# Addon-mapleCUx_HM-RFM69-RFM95-V15-001-TX.net
KiCad netlist of a schematic drawn in EAGLE
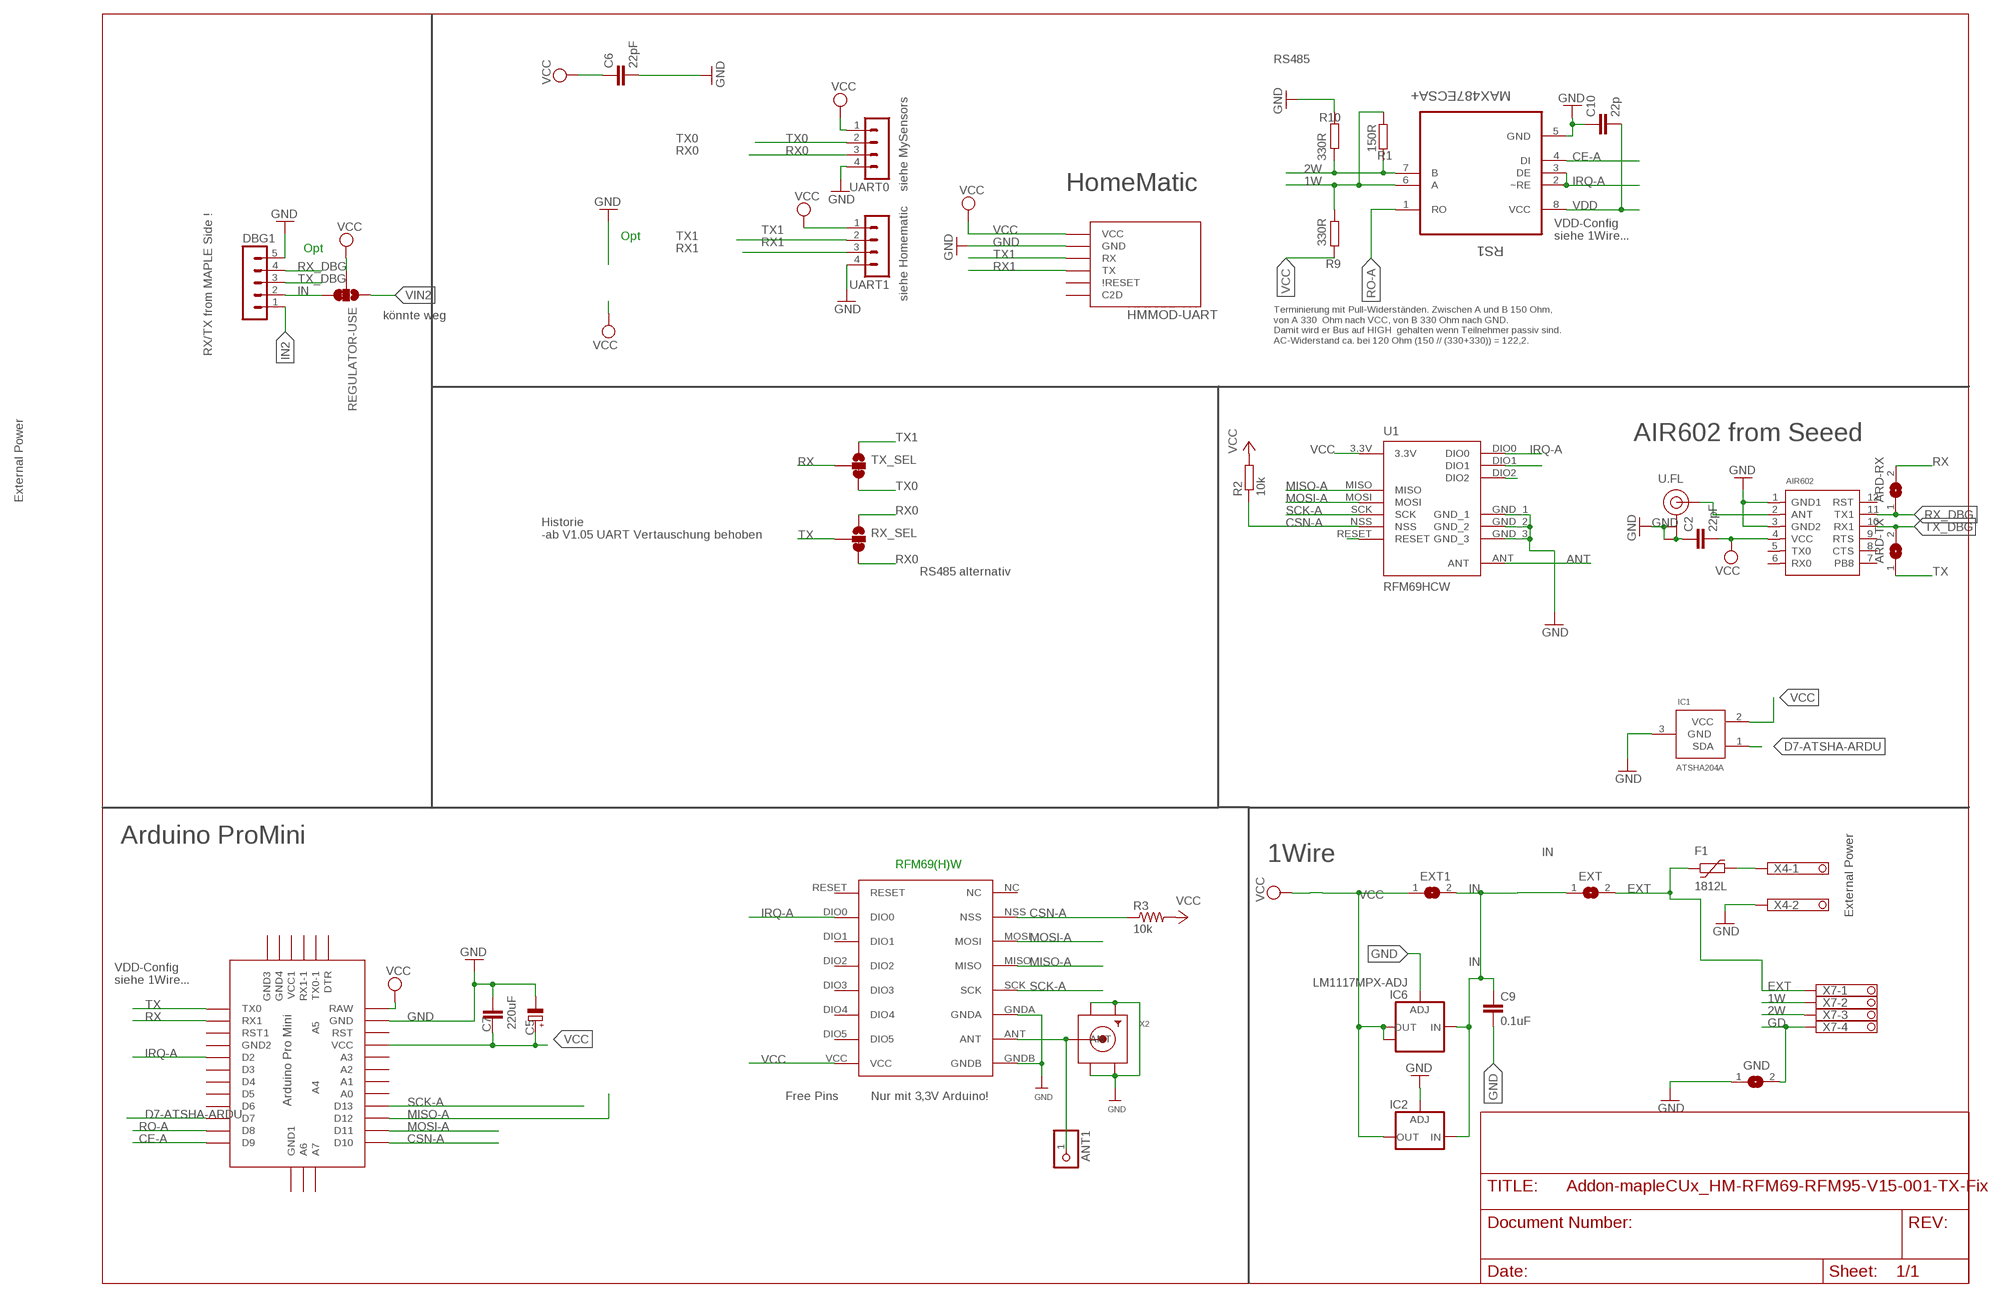
[diagram p0: schematic, sheet 1]

(export (version "E")
  (design (tool "Eeschema 10.0.6"))
  (components
    (comp (ref "AIR602")
      (value "AIR602")
      (footprint "eagle-import:MODULE12P-2.0-10X12MM")
      (libsource (lib "eagle-import") (part "AIR602"))
    )
    (comp (ref "ANT1")
      (value "PINHD-1X1")
      (footprint "eagle-import:1X01")
      (libsource (lib "eagle-import") (part "PINHD-1X1"))
    )
    (comp (ref "ARD-RX")
      (value "SJ")
      (footprint "eagle-import:SJ")
      (libsource (lib "eagle-import") (part "SJ"))
    )
    (comp (ref "ARD-TX")
      (value "SJ")
      (footprint "eagle-import:SJ")
      (libsource (lib "eagle-import") (part "SJ"))
    )
    (comp (ref "C2")
      (value "22pF")
      (footprint "eagle-import:C0805")
      (libsource (lib "eagle-import") (part "C-EUC0805"))
    )
    (comp (ref "C5")
      (value "220uF")
      (footprint "eagle-import:E5-8,5")
      (libsource (lib "eagle-import") (part "CPOL-EUE5-8.5"))
    )
    (comp (ref "C6")
      (value "22pF")
      (footprint "eagle-import:C0805")
      (libsource (lib "eagle-import") (part "C-EUC0805"))
    )
    (comp (ref "C7")
      (value "C-EUC1812")
      (footprint "eagle-import:C1812")
      (libsource (lib "eagle-import") (part "C-EUC1812"))
    )
    (comp (ref "C9")
      (value "0.1uF")
      (footprint "eagle-import:C1206")
      (libsource (lib "eagle-import") (part "C-EUC1206"))
    )
    (comp (ref "C10")
      (value "22p")
      (footprint "eagle-import:C0805")
      (libsource (lib "eagle-import") (part "C-EUC0805"))
    )
    (comp (ref "DBG1")
      (value "MA05-1")
      (footprint "eagle-import:MA05-1")
      (libsource (lib "eagle-import") (part "MA05-1"))
    )
    (comp (ref "EXT") (value "SJ") (footprint "eagle-import:SJ") (libsource (lib "eagle-import") (part "SJ")))
    (comp (ref "EXT1")
      (value "SJ")
      (footprint "eagle-import:SJ")
      (libsource (lib "eagle-import") (part "SJ"))
    )
    (comp (ref "F1")
      (value "1812L")
      (footprint "eagle-import:1812L")
      (libsource (lib "eagle-import") (part "1812L"))
    )
    (comp (ref "GND") (value "SJ") (footprint "eagle-import:SJ") (libsource (lib "eagle-import") (part "SJ")))
    (comp (ref "HMMOD-UART")
      (value "HM-MOD-UARTDIL")
      (footprint "eagle-import:HM-MOD-UART-DIL")
      (libsource (lib "eagle-import") (part "HM-MOD-UARTDIL"))
    )
    (comp (ref "IC1")
      (value "ATSHA204A")
      (footprint "eagle-import:SOT23")
      (libsource (lib "eagle-import") (part "ATSHA204A"))
    )
    (comp (ref "IC2")
      (value "LD117ADT50TR")
      (footprint "eagle-import:DPACK")
      (libsource (lib "eagle-import") (part "LD117A?DT50TR"))
    )
    (comp (ref "IC6")
      (value "LM1117MPX-ADJ")
      (footprint "eagle-import:SOT223")
      (libsource (lib "eagle-import") (part "LM1117MPX-ADJ"))
    )
    (comp (ref "R1")
      (value "150R")
      (footprint "eagle-import:R0805")
      (libsource (lib "eagle-import") (part "R-EU_R0805"))
    )
    (comp (ref "R2")
      (value "10k")
      (footprint "eagle-import:M0805")
      (libsource (lib "eagle-import") (part "R-EU_M0805"))
    )
    (comp (ref "R3")
      (value "10k")
      (footprint "eagle-import:0805")
      (libsource (lib "eagle-import") (part "RESISTOR0805-RES"))
    )
    (comp (ref "R9")
      (value "330R")
      (footprint "eagle-import:R0805")
      (libsource (lib "eagle-import") (part "R-EU_R0805"))
    )
    (comp (ref "R10")
      (value "330R")
      (footprint "eagle-import:R0805")
      (libsource (lib "eagle-import") (part "R-EU_R0805"))
    )
    (comp (ref "REGULATOR-USE")
      (value "JUMPER-SMT_3_1-NC_TRACE_SILK")
      (footprint "eagle-import:SMT-JUMPER_3_1-NC_TRACE_SILK")
      (libsource (lib "eagle-import") (part "JUMPER-SMT_3_1-NC_TRACE_SILK"))
    )
    (comp (ref "RFM69W")
      (value "RFM69HW")
      (footprint "eagle-import:RFM")
      (libsource (lib "eagle-import") (part "RFM69HW"))
    )
    (comp (ref "RS1")
      (value "MAX487ECSA+")
      (footprint "eagle-import:SOIC127P600X175-8N")
      (libsource (lib "eagle-import") (part "MAX487ECSA+"))
    )
    (comp (ref "RX_SEL")
      (value "JUMPER-SMT_3_1-NC_TRACE_SILK")
      (footprint "eagle-import:SMT-JUMPER_3_1-NC_TRACE_SILK")
      (libsource (lib "eagle-import") (part "JUMPER-SMT_3_1-NC_TRACE_SILK"))
    )
    (comp (ref "TX_SEL")
      (value "JUMPER-SMT_3_1-NC_TRACE_SILK")
      (footprint "eagle-import:SMT-JUMPER_3_1-NC_TRACE_SILK")
      (libsource (lib "eagle-import") (part "JUMPER-SMT_3_1-NC_TRACE_SILK"))
    )
    (comp (ref "U$2")
      (value "ABK-PRO-MINI")
      (footprint "eagle-import:ABK-PRO-MINI")
      (libsource (lib "eagle-import") (part "ABK-PRO-MINI"))
    )
    (comp (ref "U.FL")
      (value "U.FL")
      (footprint "eagle-import:U.FL")
      (libsource (lib "eagle-import") (part "U.FL"))
    )
    (comp (ref "U1")
      (value "RFM69HCW")
      (footprint "eagle-import:RFM69HCW-XXXS2")
      (libsource (lib "eagle-import") (part "RFM69HCW"))
    )
    (comp (ref "UART0")
      (value "MA04-1")
      (footprint "eagle-import:MA04-1")
      (libsource (lib "eagle-import") (part "MA04-1"))
    )
    (comp (ref "UART1")
      (value "MA04-1")
      (footprint "eagle-import:MA04-1")
      (libsource (lib "eagle-import") (part "MA04-1"))
    )
    (comp (ref "X2")
      (value "SMACONNECTOR_EDGE")
      (footprint "eagle-import:SMA_EDGELAUNCH")
      (libsource (lib "eagle-import") (part "SMACONNECTOR_EDGE"))
    )
    (comp (ref "X4")
      (value "1751248")
      (footprint "eagle-import:1751248")
      (libsource (lib "eagle-import") (part "1751248"))
    )
    (comp (ref "X7")
      (value "1751264")
      (footprint "eagle-import:1751264")
      (libsource (lib "eagle-import") (part "1751264"))
    )
  )
  (nets
    (net (code "1") (name "/1W") (class "Default")
      (node (ref "R1") (pin "1") (pinfunction "1_1") (pintype "passive"))
      (node (ref "R9") (pin "2") (pinfunction "2_2") (pintype "passive"))
      (node (ref "RS1") (pin "6") (pinfunction "A_6") (pintype "bidirectional"))
      (node (ref "X7") (pin "2") (pinfunction "K_2") (pintype "passive"))
    )
    (net (code "2") (name "/2W") (class "Default")
      (node (ref "R1") (pin "2") (pinfunction "2_2") (pintype "passive"))
      (node (ref "R10") (pin "1") (pinfunction "1_1") (pintype "passive"))
      (node (ref "RS1") (pin "7") (pinfunction "B_7") (pintype "bidirectional"))
      (node (ref "X7") (pin "3") (pinfunction "K_3") (pintype "passive"))
    )
    (net (code "3") (name "/ANT") (class "Default")
      (node (ref "ANT1") (pin "1") (pinfunction "1_1") (pintype "passive"))
      (node (ref "RFM69W") (pin "ANT") (pinfunction "ANT_ANT") (pintype "bidirectional"))
      (node (ref "U1") (pin "ANT") (pinfunction "ANT_ANT") (pintype "passive"))
      (node (ref "X2") (pin "P") (pinfunction "ANT_P") (pintype "bidirectional"))
    )
    (net (code "4") (name "/CE-A") (class "Default")
      (node (ref "RS1") (pin "4") (pinfunction "DI_4") (pintype "input"))
      (node (ref "U$2") (pin "D9") (pinfunction "D9_D9") (pintype "bidirectional"))
    )
    (net (code "5") (name "/CSN-A") (class "Default")
      (node (ref "R2") (pin "1") (pinfunction "1_1") (pintype "passive"))
      (node (ref "R3") (pin "1") (pinfunction "1_1") (pintype "passive"))
      (node (ref "RFM69W") (pin "NSS") (pinfunction "NSS_NSS") (pintype "bidirectional"))
      (node (ref "U$2") (pin "D10") (pinfunction "D10_D10") (pintype "bidirectional"))
      (node (ref "U1") (pin "NSS") (pinfunction "NSS_NSS") (pintype "input"))
    )
    (net (code "6") (name "/EXT") (class "Default")
      (node (ref "EXT") (pin "2") (pinfunction "2_2") (pintype "passive"))
      (node (ref "F1") (pin "P$1") (pinfunction "1_P$1") (pintype "passive"))
      (node (ref "X7") (pin "1") (pinfunction "K_1") (pintype "passive"))
    )
    (net (code "7") (name "/GD") (class "Default")
      (node (ref "GND") (pin "2") (pinfunction "2_2") (pintype "passive"))
      (node (ref "X7") (pin "4") (pinfunction "K_4") (pintype "passive"))
    )
    (net (code "8") (name "/IN") (class "Default")
      (node (ref "C9") (pin "1") (pinfunction "1_1") (pintype "passive"))
      (node (ref "DBG1") (pin "2") (pinfunction "2_2") (pintype "passive"))
      (node (ref "EXT") (pin "1") (pinfunction "1_1") (pintype "passive"))
      (node (ref "EXT1") (pin "2") (pinfunction "2_2") (pintype "passive"))
      (node (ref "IC2") (pin "3") (pinfunction "IN_3") (pintype "input"))
      (node (ref "IC6") (pin "3") (pinfunction "IN_3") (pintype "input"))
      (node (ref "REGULATOR-USE") (pin "3") (pinfunction "3_3") (pintype "passive"))
    )
    (net (code "9") (name "/IRQ-A") (class "Default")
      (node (ref "RFM69W") (pin "DIO0") (pinfunction "DIO0_DIO0") (pintype "bidirectional"))
      (node (ref "RS1") (pin "2") (pinfunction "~{RE}_2") (pintype "input"))
      (node (ref "RS1") (pin "3") (pinfunction "DE_3") (pintype "input"))
      (node (ref "U$2") (pin "D2") (pinfunction "D2_D2") (pintype "bidirectional"))
      (node (ref "U1") (pin "DIO0") (pinfunction "DIO0_DIO0") (pintype "bidirectional"))
    )
    (net (code "10") (name "/MISO-A") (class "Default")
      (node (ref "RFM69W") (pin "MISO") (pinfunction "MISO_MISO") (pintype "bidirectional"))
      (node (ref "U$2") (pin "D12") (pinfunction "D12_D12") (pintype "bidirectional"))
      (node (ref "U1") (pin "MISO") (pinfunction "MISO_MISO") (pintype "bidirectional"))
    )
    (net (code "11") (name "/MOSI-A") (class "Default")
      (node (ref "RFM69W") (pin "MOSI") (pinfunction "MOSI_MOSI") (pintype "bidirectional"))
      (node (ref "U$2") (pin "D11") (pinfunction "D11_D11") (pintype "bidirectional"))
      (node (ref "U1") (pin "MOSI") (pinfunction "MOSI_MOSI") (pintype "input"))
    )
    (net (code "12") (name "/RX") (class "Default")
      (node (ref "ARD-RX") (pin "2") (pinfunction "2_2") (pintype "passive"))
      (node (ref "TX_SEL") (pin "2") (pinfunction "2_2") (pintype "passive"))
      (node (ref "U$2") (pin "RX1") (pinfunction "RX1_RX1") (pintype "bidirectional"))
    )
    (net (code "13") (name "/RX0") (class "Default")
      (node (ref "RX_SEL") (pin "1") (pinfunction "1_1") (pintype "passive"))
      (node (ref "RX_SEL") (pin "3") (pinfunction "3_3") (pintype "passive"))
      (node (ref "UART0") (pin "3") (pinfunction "3_3") (pintype "passive"))
    )
    (net (code "14") (name "/RX1") (class "Default")
      (node (ref "HMMOD-UART") (pin "5") (pinfunction "TX_5") (pintype "bidirectional"))
      (node (ref "UART1") (pin "3") (pinfunction "3_3") (pintype "passive"))
    )
    (net (code "15") (name "/SCK-A") (class "Default")
      (node (ref "RFM69W") (pin "SCK") (pinfunction "SCK_SCK") (pintype "bidirectional"))
      (node (ref "U$2") (pin "D13") (pinfunction "D13_D13") (pintype "bidirectional"))
      (node (ref "U1") (pin "SCK") (pinfunction "SCK_SCK") (pintype "input"))
    )
    (net (code "16") (name "/TX") (class "Default")
      (node (ref "ARD-TX") (pin "1") (pinfunction "1_1") (pintype "passive"))
      (node (ref "RX_SEL") (pin "2") (pinfunction "2_2") (pintype "passive"))
      (node (ref "U$2") (pin "TX0") (pinfunction "TX0_TX0") (pintype "bidirectional"))
    )
    (net (code "17") (name "/TX0") (class "Default")
      (node (ref "TX_SEL") (pin "3") (pinfunction "3_3") (pintype "passive"))
      (node (ref "UART0") (pin "2") (pinfunction "2_2") (pintype "passive"))
    )
    (net (code "18") (name "/TX1") (class "Default")
      (node (ref "HMMOD-UART") (pin "6") (pinfunction "RX_6") (pintype "bidirectional"))
      (node (ref "TX_SEL") (pin "1") (pinfunction "1_1") (pintype "passive"))
      (node (ref "UART1") (pin "2") (pinfunction "2_2") (pintype "passive"))
    )
    (net (code "19") (name "/VDD") (class "Default")
      (node (ref "C10") (pin "2") (pinfunction "2_2") (pintype "passive"))
      (node (ref "RS1") (pin "8") (pinfunction "VCC_8") (pintype "power_in"))
    )
    (net (code "20") (name "D7-ATSHA-ARDU") (class "Default")
      (node (ref "IC1") (pin "1") (pinfunction "SDA_1") (pintype "bidirectional"))
      (node (ref "U$2") (pin "D7") (pinfunction "D7_D7") (pintype "bidirectional"))
    )
    (net (code "21") (name "GND") (class "Default")
      (node (ref "AIR602") (pin "1") (pinfunction "GND1_1") (pintype "bidirectional"))
      (node (ref "AIR602") (pin "3") (pinfunction "GND2_3") (pintype "bidirectional"))
      (node (ref "C10") (pin "1") (pinfunction "1_1") (pintype "passive"))
      (node (ref "C2") (pin "1") (pinfunction "1_1") (pintype "passive"))
      (node (ref "C5") (pin "-") (pinfunction "-_-") (pintype "passive"))
      (node (ref "C6") (pin "2") (pinfunction "2_2") (pintype "passive"))
      (node (ref "C7") (pin "1") (pinfunction "1_1") (pintype "passive"))
      (node (ref "C9") (pin "2") (pinfunction "2_2") (pintype "passive"))
      (node (ref "DBG1") (pin "5") (pinfunction "5_5") (pintype "passive"))
      (node (ref "GND") (pin "1") (pinfunction "1_1") (pintype "passive"))
      (node (ref "HMMOD-UART") (pin "2") (pinfunction "GND_2") (pintype "power_in"))
      (node (ref "IC1") (pin "3") (pinfunction "GND_3") (pintype "bidirectional"))
      (node (ref "IC2") (pin "1") (pinfunction "ADJ_1") (pintype "input"))
      (node (ref "IC6") (pin "1") (pinfunction "ADJ_1") (pintype "input"))
      (node (ref "R10") (pin "2") (pinfunction "2_2") (pintype "passive"))
      (node (ref "RFM69W") (pin "GNDA") (pinfunction "GNDA_GNDA") (pintype "bidirectional"))
      (node (ref "RFM69W") (pin "GNDB") (pinfunction "GNDB_GNDB") (pintype "bidirectional"))
      (node (ref "RS1") (pin "5") (pinfunction "GND_5") (pintype "passive"))
      (node (ref "U$2") (pin "GND") (pinfunction "GND_GND") (pintype "bidirectional"))
      (node (ref "U.FL") (pin "1") (pinfunction "GND_1") (pintype "bidirectional"))
      (node (ref "U.FL") (pin "2") (pinfunction "GND_2") (pintype "bidirectional"))
      (node (ref "U1") (pin "GND_1") (pinfunction "GND_1_GND_1") (pintype "power_in"))
      (node (ref "U1") (pin "GND_2") (pinfunction "GND_2_GND_2") (pintype "power_in"))
      (node (ref "U1") (pin "GND_3") (pinfunction "GND_3_GND_3") (pintype "power_in"))
      (node (ref "UART0") (pin "4") (pinfunction "4_4") (pintype "passive"))
      (node (ref "UART1") (pin "4") (pinfunction "4_4") (pintype "passive"))
      (node (ref "X2") (pin "GND@1") (pinfunction "GND4_GND@1") (pintype "power_in"))
      (node (ref "X2") (pin "GND@2") (pinfunction "GND3_GND@2") (pintype "power_in"))
      (node (ref "X2") (pin "GND@3") (pinfunction "GND2_GND@3") (pintype "power_in"))
      (node (ref "X2") (pin "GND@4") (pinfunction "GND1_GND@4") (pintype "power_in"))
      (node (ref "X4") (pin "2") (pinfunction "K_2") (pintype "passive"))
    )
    (net (code "22") (name "IN2") (class "Default")
      (node (ref "DBG1") (pin "1") (pinfunction "1_1") (pintype "passive"))
    )
    (net (code "23") (name "Net-(AIR602-ANT)") (class "Default")
      (node (ref "AIR602") (pin "2") (pinfunction "ANT_2") (pintype "bidirectional"))
      (node (ref "U.FL") (pin "FEED") (pinfunction "SIGNAL_FEED") (pintype "bidirectional"))
    )
    (net (code "24") (name "Net-(F1-2)") (class "Default")
      (node (ref "F1") (pin "P$2") (pinfunction "2_P$2") (pintype "passive"))
      (node (ref "X4") (pin "1") (pinfunction "K_1") (pintype "passive"))
    )
    (net (code "25") (name "RO-A") (class "Default")
      (node (ref "RS1") (pin "1") (pinfunction "RO_1") (pintype "output"))
      (node (ref "U$2") (pin "D8") (pinfunction "D8_D8") (pintype "bidirectional"))
    )
    (net (code "26") (name "RX_DBG") (class "Default")
      (node (ref "AIR602") (pin "11") (pinfunction "TX1_11") (pintype "bidirectional"))
      (node (ref "ARD-RX") (pin "1") (pinfunction "1_1") (pintype "passive"))
      (node (ref "DBG1") (pin "4") (pinfunction "4_4") (pintype "passive"))
    )
    (net (code "27") (name "TX_DBG") (class "Default")
      (node (ref "AIR602") (pin "10") (pinfunction "RX1_10") (pintype "bidirectional"))
      (node (ref "ARD-TX") (pin "2") (pinfunction "2_2") (pintype "passive"))
      (node (ref "DBG1") (pin "3") (pinfunction "3_3") (pintype "passive"))
    )
    (net (code "28") (name "VCC") (class "Default")
      (node (ref "AIR602") (pin "4") (pinfunction "VCC_4") (pintype "bidirectional"))
      (node (ref "C2") (pin "2") (pinfunction "2_2") (pintype "passive"))
      (node (ref "C5") (pin "+") (pinfunction "+_+") (pintype "passive"))
      (node (ref "C6") (pin "1") (pinfunction "1_1") (pintype "passive"))
      (node (ref "C7") (pin "2") (pinfunction "2_2") (pintype "passive"))
      (node (ref "EXT1") (pin "1") (pinfunction "1_1") (pintype "passive"))
      (node (ref "HMMOD-UART") (pin "1") (pinfunction "VCC_1") (pintype "power_in"))
      (node (ref "IC1") (pin "2") (pinfunction "VCC_2") (pintype "bidirectional"))
      (node (ref "IC2") (pin "4") (pinfunction "OUT_4") (pintype "passive"))
      (node (ref "IC6") (pin "2") (pinfunction "OUT_2") (pintype "passive"))
      (node (ref "IC6") (pin "TAB") (pinfunction "OUT1_TAB") (pintype "passive"))
      (node (ref "R2") (pin "2") (pinfunction "2_2") (pintype "passive"))
      (node (ref "R3") (pin "2") (pinfunction "2_2") (pintype "passive"))
      (node (ref "R9") (pin "1") (pinfunction "1_1") (pintype "passive"))
      (node (ref "REGULATOR-USE") (pin "2") (pinfunction "2_2") (pintype "passive"))
      (node (ref "RFM69W") (pin "VCC") (pinfunction "VCC_VCC") (pintype "bidirectional"))
      (node (ref "U$2") (pin "RAW") (pinfunction "RAW_RAW") (pintype "bidirectional"))
      (node (ref "U$2") (pin "VCC") (pinfunction "VCC_VCC") (pintype "bidirectional"))
      (node (ref "U1") (pin "3.3V") (pinfunction "3.3V_3.3V") (pintype "power_in"))
      (node (ref "UART0") (pin "1") (pinfunction "1_1") (pintype "passive"))
      (node (ref "UART1") (pin "1") (pinfunction "1_1") (pintype "passive"))
    )
    (net (code "29") (name "VIN2") (class "Default")
      (node (ref "REGULATOR-USE") (pin "1") (pinfunction "1_1") (pintype "passive"))
    )
    (net (code "30") (name "unconnected-(AIR602-CTS-Pad8)") (class "Default")
      (node (ref "AIR602") (pin "8") (pinfunction "CTS_8") (pintype "bidirectional"))
    )
    (net (code "31") (name "unconnected-(AIR602-PB8-Pad7)") (class "Default")
      (node (ref "AIR602") (pin "7") (pinfunction "PB8_7") (pintype "bidirectional"))
    )
    (net (code "32") (name "unconnected-(AIR602-RST-Pad12)") (class "Default")
      (node (ref "AIR602") (pin "12") (pinfunction "RST_12") (pintype "bidirectional"))
    )
    (net (code "33") (name "unconnected-(AIR602-RTS-Pad9)") (class "Default")
      (node (ref "AIR602") (pin "9") (pinfunction "RTS_9") (pintype "bidirectional"))
    )
    (net (code "34") (name "unconnected-(AIR602-RX0-Pad6)") (class "Default")
      (node (ref "AIR602") (pin "6") (pinfunction "RX0_6") (pintype "bidirectional"))
    )
    (net (code "35") (name "unconnected-(AIR602-TX0-Pad5)") (class "Default")
      (node (ref "AIR602") (pin "5") (pinfunction "TX0_5") (pintype "bidirectional"))
    )
    (net (code "36") (name "unconnected-(HMMOD-UART-C2D-Pad3)") (class "Default")
      (node (ref "HMMOD-UART") (pin "3") (pinfunction "C2D_3") (pintype "bidirectional"))
    )
    (net (code "37") (name "unconnected-(HMMOD-UART-\\~{RESET}-Pad4)") (class "Default")
      (node (ref "HMMOD-UART") (pin "4") (pinfunction "\\~{RESET}_4") (pintype "bidirectional"))
    )
    (net (code "38") (name "unconnected-(RFM69W-PadDIO1)") (class "Default")
      (node (ref "RFM69W") (pin "DIO1") (pinfunction "DIO1_DIO1") (pintype "bidirectional"))
    )
    (net (code "39") (name "unconnected-(RFM69W-PadDIO2)") (class "Default")
      (node (ref "RFM69W") (pin "DIO2") (pinfunction "DIO2_DIO2") (pintype "bidirectional"))
    )
    (net (code "40") (name "unconnected-(RFM69W-PadDIO3)") (class "Default")
      (node (ref "RFM69W") (pin "DIO3") (pinfunction "DIO3_DIO3") (pintype "bidirectional"))
    )
    (net (code "41") (name "unconnected-(RFM69W-PadDIO4)") (class "Default")
      (node (ref "RFM69W") (pin "DIO4") (pinfunction "DIO4_DIO4") (pintype "bidirectional"))
    )
    (net (code "42") (name "unconnected-(RFM69W-PadDIO5)") (class "Default")
      (node (ref "RFM69W") (pin "DIO5") (pinfunction "DIO5_DIO5") (pintype "bidirectional"))
    )
    (net (code "43") (name "unconnected-(RFM69W-PadNC)") (class "Default")
      (node (ref "RFM69W") (pin "NC") (pinfunction "NC_NC") (pintype "bidirectional"))
    )
    (net (code "44") (name "unconnected-(RFM69W-PadRESET)") (class "Default")
      (node (ref "RFM69W") (pin "RESET") (pinfunction "RESET_RESET") (pintype "bidirectional"))
    )
    (net (code "45") (name "unconnected-(U$2-GND1-PadGND4)") (class "Default")
      (node (ref "U$2") (pin "GND4") (pinfunction "GND1_GND4") (pintype "bidirectional"))
    )
    (net (code "46") (name "unconnected-(U$2-GND2-PadGND1)") (class "Default")
      (node (ref "U$2") (pin "GND1") (pinfunction "GND2_GND1") (pintype "bidirectional"))
    )
    (net (code "47") (name "unconnected-(U$2-GND3-PadGND2)") (class "Default")
      (node (ref "U$2") (pin "GND2") (pinfunction "GND3_GND2") (pintype "bidirectional"))
    )
    (net (code "48") (name "unconnected-(U$2-GND4-PadGND3)") (class "Default")
      (node (ref "U$2") (pin "GND3") (pinfunction "GND4_GND3") (pintype "bidirectional"))
    )
    (net (code "49") (name "unconnected-(U$2-PadA0)") (class "Default")
      (node (ref "U$2") (pin "A0") (pinfunction "A0_A0") (pintype "bidirectional"))
    )
    (net (code "50") (name "unconnected-(U$2-PadA1)") (class "Default")
      (node (ref "U$2") (pin "A1") (pinfunction "A1_A1") (pintype "bidirectional"))
    )
    (net (code "51") (name "unconnected-(U$2-PadA2)") (class "Default")
      (node (ref "U$2") (pin "A2") (pinfunction "A2_A2") (pintype "bidirectional"))
    )
    (net (code "52") (name "unconnected-(U$2-PadA3)") (class "Default")
      (node (ref "U$2") (pin "A3") (pinfunction "A3_A3") (pintype "bidirectional"))
    )
    (net (code "53") (name "unconnected-(U$2-PadA4)") (class "Default")
      (node (ref "U$2") (pin "A4") (pinfunction "A4_A4") (pintype "bidirectional"))
    )
    (net (code "54") (name "unconnected-(U$2-PadA5)") (class "Default")
      (node (ref "U$2") (pin "A5") (pinfunction "A5_A5") (pintype "bidirectional"))
    )
    (net (code "55") (name "unconnected-(U$2-PadA6)") (class "Default")
      (node (ref "U$2") (pin "A6") (pinfunction "A6_A6") (pintype "bidirectional"))
    )
    (net (code "56") (name "unconnected-(U$2-PadA7)") (class "Default")
      (node (ref "U$2") (pin "A7") (pinfunction "A7_A7") (pintype "bidirectional"))
    )
    (net (code "57") (name "unconnected-(U$2-PadD3)") (class "Default")
      (node (ref "U$2") (pin "D3") (pinfunction "D3_D3") (pintype "bidirectional"))
    )
    (net (code "58") (name "unconnected-(U$2-PadD4)") (class "Default")
      (node (ref "U$2") (pin "D4") (pinfunction "D4_D4") (pintype "bidirectional"))
    )
    (net (code "59") (name "unconnected-(U$2-PadD5)") (class "Default")
      (node (ref "U$2") (pin "D5") (pinfunction "D5_D5") (pintype "bidirectional"))
    )
    (net (code "60") (name "unconnected-(U$2-PadD6)") (class "Default")
      (node (ref "U$2") (pin "D6") (pinfunction "D6_D6") (pintype "bidirectional"))
    )
    (net (code "61") (name "unconnected-(U$2-PadDTR)") (class "Default")
      (node (ref "U$2") (pin "DTR") (pinfunction "DTR_DTR") (pintype "bidirectional"))
    )
    (net (code "62") (name "unconnected-(U$2-PadRST)") (class "Default")
      (node (ref "U$2") (pin "RST") (pinfunction "RST_RST") (pintype "bidirectional"))
    )
    (net (code "63") (name "unconnected-(U$2-PadRST1)") (class "Default")
      (node (ref "U$2") (pin "RST1") (pinfunction "RST1_RST1") (pintype "bidirectional"))
    )
    (net (code "64") (name "unconnected-(U$2-PadRX1-1)") (class "Default")
      (node (ref "U$2") (pin "RX1-1") (pinfunction "RX1-1_RX1-1") (pintype "bidirectional"))
    )
    (net (code "65") (name "unconnected-(U$2-PadTX0-1)") (class "Default")
      (node (ref "U$2") (pin "TX0-1") (pinfunction "TX0-1_TX0-1") (pintype "bidirectional"))
    )
    (net (code "66") (name "unconnected-(U$2-PadVCC1)") (class "Default")
      (node (ref "U$2") (pin "VCC1") (pinfunction "VCC1_VCC1") (pintype "bidirectional"))
    )
    (net (code "67") (name "unconnected-(U1-PadDIO1)") (class "Default")
      (node (ref "U1") (pin "DIO1") (pinfunction "DIO1_DIO1") (pintype "bidirectional"))
    )
    (net (code "68") (name "unconnected-(U1-PadDIO2)") (class "Default")
      (node (ref "U1") (pin "DIO2") (pinfunction "DIO2_DIO2") (pintype "bidirectional"))
    )
    (net (code "69") (name "unconnected-(U1-PadRESET)") (class "Default")
      (node (ref "U1") (pin "RESET") (pinfunction "RESET_RESET") (pintype "input"))
    )
  )
)
